# LED_V2.net
KiCad netlist of a schematic drawn in Altium Designer
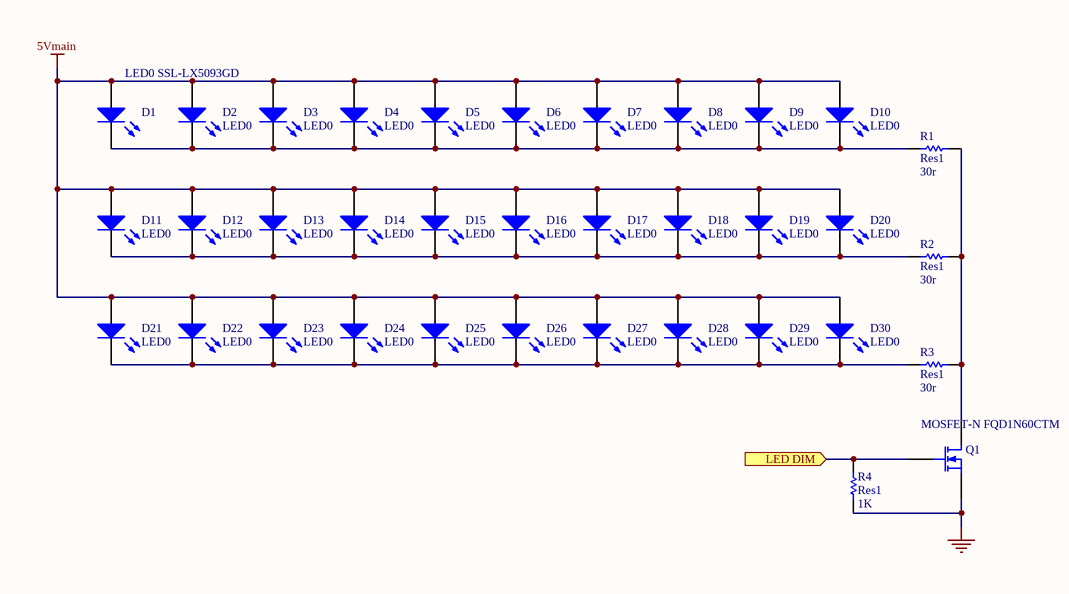
[diagram p0: LED_V2.SchDoc]

(export (version "E")
  (design (tool "Eeschema 10.0.6"))
  (components
    (comp (ref "D1")
      (value "LED0 SSL-LX5093GD")
      (footprint "LED-0")
      (description "Typical INFRARED GaAs LED")
      (fields (field (name "PUBLISHER") "Altium Limited"))
      (libsource (lib "Miscellaneous Devices") (part "LED0"))
    )
    (comp (ref "D2")
      (value "LED0")
      (footprint "LED-0")
      (description "Typical INFRARED GaAs LED")
      (fields (field (name "PUBLISHER") "Altium Limited"))
      (libsource (lib "Miscellaneous Devices") (part "LED0"))
    )
    (comp (ref "D3")
      (value "LED0")
      (footprint "LED-0")
      (description "Typical INFRARED GaAs LED")
      (fields (field (name "PUBLISHER") "Altium Limited"))
      (libsource (lib "Miscellaneous Devices") (part "LED0"))
    )
    (comp (ref "D4")
      (value "LED0")
      (footprint "LED-0")
      (description "Typical INFRARED GaAs LED")
      (fields (field (name "PUBLISHER") "Altium Limited"))
      (libsource (lib "Miscellaneous Devices") (part "LED0"))
    )
    (comp (ref "D5")
      (value "LED0")
      (footprint "LED-0")
      (description "Typical INFRARED GaAs LED")
      (fields (field (name "PUBLISHER") "Altium Limited"))
      (libsource (lib "Miscellaneous Devices") (part "LED0"))
    )
    (comp (ref "D6")
      (value "LED0")
      (footprint "LED-0")
      (description "Typical INFRARED GaAs LED")
      (fields (field (name "PUBLISHER") "Altium Limited"))
      (libsource (lib "Miscellaneous Devices") (part "LED0"))
    )
    (comp (ref "D7")
      (value "LED0")
      (footprint "LED-0")
      (description "Typical INFRARED GaAs LED")
      (fields (field (name "PUBLISHER") "Altium Limited"))
      (libsource (lib "Miscellaneous Devices") (part "LED0"))
    )
    (comp (ref "D8")
      (value "LED0")
      (footprint "LED-0")
      (description "Typical INFRARED GaAs LED")
      (fields (field (name "PUBLISHER") "Altium Limited"))
      (libsource (lib "Miscellaneous Devices") (part "LED0"))
    )
    (comp (ref "D9")
      (value "LED0")
      (footprint "LED-0")
      (description "Typical INFRARED GaAs LED")
      (fields (field (name "PUBLISHER") "Altium Limited"))
      (libsource (lib "Miscellaneous Devices") (part "LED0"))
    )
    (comp (ref "D10")
      (value "LED0")
      (footprint "LED-0")
      (description "Typical INFRARED GaAs LED")
      (fields (field (name "PUBLISHER") "Altium Limited"))
      (libsource (lib "Miscellaneous Devices") (part "LED0"))
    )
    (comp (ref "D11")
      (value "LED0")
      (footprint "LED-0")
      (description "Typical INFRARED GaAs LED")
      (fields (field (name "PUBLISHER") "Altium Limited"))
      (libsource (lib "Miscellaneous Devices") (part "LED0"))
    )
    (comp (ref "D12")
      (value "LED0")
      (footprint "LED-0")
      (description "Typical INFRARED GaAs LED")
      (fields (field (name "PUBLISHER") "Altium Limited"))
      (libsource (lib "Miscellaneous Devices") (part "LED0"))
    )
    (comp (ref "D13")
      (value "LED0")
      (footprint "LED-0")
      (description "Typical INFRARED GaAs LED")
      (fields (field (name "PUBLISHER") "Altium Limited"))
      (libsource (lib "Miscellaneous Devices") (part "LED0"))
    )
    (comp (ref "D14")
      (value "LED0")
      (footprint "LED-0")
      (description "Typical INFRARED GaAs LED")
      (fields (field (name "PUBLISHER") "Altium Limited"))
      (libsource (lib "Miscellaneous Devices") (part "LED0"))
    )
    (comp (ref "D15")
      (value "LED0")
      (footprint "LED-0")
      (description "Typical INFRARED GaAs LED")
      (fields (field (name "PUBLISHER") "Altium Limited"))
      (libsource (lib "Miscellaneous Devices") (part "LED0"))
    )
    (comp (ref "D16")
      (value "LED0")
      (footprint "LED-0")
      (description "Typical INFRARED GaAs LED")
      (fields (field (name "PUBLISHER") "Altium Limited"))
      (libsource (lib "Miscellaneous Devices") (part "LED0"))
    )
    (comp (ref "D17")
      (value "LED0")
      (footprint "LED-0")
      (description "Typical INFRARED GaAs LED")
      (fields (field (name "PUBLISHER") "Altium Limited"))
      (libsource (lib "Miscellaneous Devices") (part "LED0"))
    )
    (comp (ref "D18")
      (value "LED0")
      (footprint "LED-0")
      (description "Typical INFRARED GaAs LED")
      (fields (field (name "PUBLISHER") "Altium Limited"))
      (libsource (lib "Miscellaneous Devices") (part "LED0"))
    )
    (comp (ref "D19")
      (value "LED0")
      (footprint "LED-0")
      (description "Typical INFRARED GaAs LED")
      (fields (field (name "PUBLISHER") "Altium Limited"))
      (libsource (lib "Miscellaneous Devices") (part "LED0"))
    )
    (comp (ref "D20")
      (value "LED0")
      (footprint "LED-0")
      (description "Typical INFRARED GaAs LED")
      (fields (field (name "PUBLISHER") "Altium Limited"))
      (libsource (lib "Miscellaneous Devices") (part "LED0"))
    )
    (comp (ref "D21")
      (value "LED0")
      (footprint "LED-0")
      (description "Typical INFRARED GaAs LED")
      (fields (field (name "PUBLISHER") "Altium Limited"))
      (libsource (lib "Miscellaneous Devices") (part "LED0"))
    )
    (comp (ref "D22")
      (value "LED0")
      (footprint "LED-0")
      (description "Typical INFRARED GaAs LED")
      (fields (field (name "PUBLISHER") "Altium Limited"))
      (libsource (lib "Miscellaneous Devices") (part "LED0"))
    )
    (comp (ref "D23")
      (value "LED0")
      (footprint "LED-0")
      (description "Typical INFRARED GaAs LED")
      (fields (field (name "PUBLISHER") "Altium Limited"))
      (libsource (lib "Miscellaneous Devices") (part "LED0"))
    )
    (comp (ref "D24")
      (value "LED0")
      (footprint "LED-0")
      (description "Typical INFRARED GaAs LED")
      (fields (field (name "PUBLISHER") "Altium Limited"))
      (libsource (lib "Miscellaneous Devices") (part "LED0"))
    )
    (comp (ref "D25")
      (value "LED0")
      (footprint "LED-0")
      (description "Typical INFRARED GaAs LED")
      (fields (field (name "PUBLISHER") "Altium Limited"))
      (libsource (lib "Miscellaneous Devices") (part "LED0"))
    )
    (comp (ref "D26")
      (value "LED0")
      (footprint "LED-0")
      (description "Typical INFRARED GaAs LED")
      (fields (field (name "PUBLISHER") "Altium Limited"))
      (libsource (lib "Miscellaneous Devices") (part "LED0"))
    )
    (comp (ref "D27")
      (value "LED0")
      (footprint "LED-0")
      (description "Typical INFRARED GaAs LED")
      (fields (field (name "PUBLISHER") "Altium Limited"))
      (libsource (lib "Miscellaneous Devices") (part "LED0"))
    )
    (comp (ref "D28")
      (value "LED0")
      (footprint "LED-0")
      (description "Typical INFRARED GaAs LED")
      (fields (field (name "PUBLISHER") "Altium Limited"))
      (libsource (lib "Miscellaneous Devices") (part "LED0"))
    )
    (comp (ref "D29")
      (value "LED0")
      (footprint "LED-0")
      (description "Typical INFRARED GaAs LED")
      (fields (field (name "PUBLISHER") "Altium Limited"))
      (libsource (lib "Miscellaneous Devices") (part "LED0"))
    )
    (comp (ref "D30")
      (value "LED0")
      (footprint "LED-0")
      (description "Typical INFRARED GaAs LED")
      (fields (field (name "PUBLISHER") "Altium Limited"))
      (libsource (lib "Miscellaneous Devices") (part "LED0"))
    )
    (comp (ref "Q1")
      (value "MOSFET-N FQD1N60CTM")
      (footprint "MarvinPcbLib2:TO252")
      (description "N-Channel MOSFET")
      (fields (field (name "PUBLISHER") "Altium Limited"))
      (libsource (lib "Miscellaneous Devices") (part "MOSFET-N"))
    )
    (comp (ref "R1")
      (value "Res1")
      (footprint "AXIAL-0.3")
      (description "Resistor")
      (fields (field (name "ALTIUM_VALUE") "30r") (field (name "PUBLISHER") "Altium Limited"))
      (libsource (lib "Miscellaneous Devices") (part "Res1"))
    )
    (comp (ref "R2")
      (value "Res1")
      (footprint "AXIAL-0.3")
      (description "Resistor")
      (fields (field (name "ALTIUM_VALUE") "30r") (field (name "PUBLISHER") "Altium Limited"))
      (libsource (lib "Miscellaneous Devices") (part "Res1"))
    )
    (comp (ref "R3")
      (value "Res1")
      (footprint "AXIAL-0.3")
      (description "Resistor")
      (fields (field (name "ALTIUM_VALUE") "30r") (field (name "PUBLISHER") "Altium Limited"))
      (libsource (lib "Miscellaneous Devices") (part "Res1"))
    )
    (comp (ref "R4")
      (value "Res1")
      (footprint "AXIAL-0.3")
      (description "Resistor")
      (fields (field (name "ALTIUM_VALUE") "1K") (field (name "PUBLISHER") "Altium Limited"))
      (libsource (lib "Miscellaneous Devices") (part "Res1"))
    )
  )
  (nets
    (net (code "1") (name "/LED DIM") (class "Default")
      (node (ref "Q1") (pin "1") (pinfunction "G_1") (pintype "passive"))
      (node (ref "R4") (pin "2") (pinfunction "2_2") (pintype "passive"))
    )
    (net (code "2") (name "5Vmain") (class "Default")
      (node (ref "D1") (pin "1") (pinfunction "A_1") (pintype "passive"))
      (node (ref "D10") (pin "1") (pinfunction "A_1") (pintype "passive"))
      (node (ref "D11") (pin "1") (pinfunction "A_1") (pintype "passive"))
      (node (ref "D12") (pin "1") (pinfunction "A_1") (pintype "passive"))
      (node (ref "D13") (pin "1") (pinfunction "A_1") (pintype "passive"))
      (node (ref "D14") (pin "1") (pinfunction "A_1") (pintype "passive"))
      (node (ref "D15") (pin "1") (pinfunction "A_1") (pintype "passive"))
      (node (ref "D16") (pin "1") (pinfunction "A_1") (pintype "passive"))
      (node (ref "D17") (pin "1") (pinfunction "A_1") (pintype "passive"))
      (node (ref "D18") (pin "1") (pinfunction "A_1") (pintype "passive"))
      (node (ref "D19") (pin "1") (pinfunction "A_1") (pintype "passive"))
      (node (ref "D2") (pin "1") (pinfunction "A_1") (pintype "passive"))
      (node (ref "D20") (pin "1") (pinfunction "A_1") (pintype "passive"))
      (node (ref "D21") (pin "1") (pinfunction "A_1") (pintype "passive"))
      (node (ref "D22") (pin "1") (pinfunction "A_1") (pintype "passive"))
      (node (ref "D23") (pin "1") (pinfunction "A_1") (pintype "passive"))
      (node (ref "D24") (pin "1") (pinfunction "A_1") (pintype "passive"))
      (node (ref "D25") (pin "1") (pinfunction "A_1") (pintype "passive"))
      (node (ref "D26") (pin "1") (pinfunction "A_1") (pintype "passive"))
      (node (ref "D27") (pin "1") (pinfunction "A_1") (pintype "passive"))
      (node (ref "D28") (pin "1") (pinfunction "A_1") (pintype "passive"))
      (node (ref "D29") (pin "1") (pinfunction "A_1") (pintype "passive"))
      (node (ref "D3") (pin "1") (pinfunction "A_1") (pintype "passive"))
      (node (ref "D30") (pin "1") (pinfunction "A_1") (pintype "passive"))
      (node (ref "D4") (pin "1") (pinfunction "A_1") (pintype "passive"))
      (node (ref "D5") (pin "1") (pinfunction "A_1") (pintype "passive"))
      (node (ref "D6") (pin "1") (pinfunction "A_1") (pintype "passive"))
      (node (ref "D7") (pin "1") (pinfunction "A_1") (pintype "passive"))
      (node (ref "D8") (pin "1") (pinfunction "A_1") (pintype "passive"))
      (node (ref "D9") (pin "1") (pinfunction "A_1") (pintype "passive"))
    )
    (net (code "3") (name "GND") (class "Default")
      (node (ref "Q1") (pin "3") (pinfunction "S_3") (pintype "passive"))
      (node (ref "R4") (pin "1") (pinfunction "1_1") (pintype "passive"))
    )
    (net (code "4") (name "Net-(D1-K)") (class "Default")
      (node (ref "D1") (pin "2") (pinfunction "K_2") (pintype "passive"))
      (node (ref "D10") (pin "2") (pinfunction "K_2") (pintype "passive"))
      (node (ref "D2") (pin "2") (pinfunction "K_2") (pintype "passive"))
      (node (ref "D3") (pin "2") (pinfunction "K_2") (pintype "passive"))
      (node (ref "D4") (pin "2") (pinfunction "K_2") (pintype "passive"))
      (node (ref "D5") (pin "2") (pinfunction "K_2") (pintype "passive"))
      (node (ref "D6") (pin "2") (pinfunction "K_2") (pintype "passive"))
      (node (ref "D7") (pin "2") (pinfunction "K_2") (pintype "passive"))
      (node (ref "D8") (pin "2") (pinfunction "K_2") (pintype "passive"))
      (node (ref "D9") (pin "2") (pinfunction "K_2") (pintype "passive"))
      (node (ref "R1") (pin "1") (pinfunction "1_1") (pintype "passive"))
    )
    (net (code "5") (name "Net-(D11-K)") (class "Default")
      (node (ref "D11") (pin "2") (pinfunction "K_2") (pintype "passive"))
      (node (ref "D12") (pin "2") (pinfunction "K_2") (pintype "passive"))
      (node (ref "D13") (pin "2") (pinfunction "K_2") (pintype "passive"))
      (node (ref "D14") (pin "2") (pinfunction "K_2") (pintype "passive"))
      (node (ref "D15") (pin "2") (pinfunction "K_2") (pintype "passive"))
      (node (ref "D16") (pin "2") (pinfunction "K_2") (pintype "passive"))
      (node (ref "D17") (pin "2") (pinfunction "K_2") (pintype "passive"))
      (node (ref "D18") (pin "2") (pinfunction "K_2") (pintype "passive"))
      (node (ref "D19") (pin "2") (pinfunction "K_2") (pintype "passive"))
      (node (ref "D20") (pin "2") (pinfunction "K_2") (pintype "passive"))
      (node (ref "R2") (pin "1") (pinfunction "1_1") (pintype "passive"))
    )
    (net (code "6") (name "Net-(D21-K)") (class "Default")
      (node (ref "D21") (pin "2") (pinfunction "K_2") (pintype "passive"))
      (node (ref "D22") (pin "2") (pinfunction "K_2") (pintype "passive"))
      (node (ref "D23") (pin "2") (pinfunction "K_2") (pintype "passive"))
      (node (ref "D24") (pin "2") (pinfunction "K_2") (pintype "passive"))
      (node (ref "D25") (pin "2") (pinfunction "K_2") (pintype "passive"))
      (node (ref "D26") (pin "2") (pinfunction "K_2") (pintype "passive"))
      (node (ref "D27") (pin "2") (pinfunction "K_2") (pintype "passive"))
      (node (ref "D28") (pin "2") (pinfunction "K_2") (pintype "passive"))
      (node (ref "D29") (pin "2") (pinfunction "K_2") (pintype "passive"))
      (node (ref "D30") (pin "2") (pinfunction "K_2") (pintype "passive"))
      (node (ref "R3") (pin "1") (pinfunction "1_1") (pintype "passive"))
    )
    (net (code "7") (name "Net-(Q1-D)") (class "Default")
      (node (ref "Q1") (pin "2") (pinfunction "D_2") (pintype "passive"))
      (node (ref "R1") (pin "2") (pinfunction "2_2") (pintype "passive"))
      (node (ref "R2") (pin "2") (pinfunction "2_2") (pintype "passive"))
      (node (ref "R3") (pin "2") (pinfunction "2_2") (pintype "passive"))
    )
  )
)
